# 411618_029_3_5.net
KiCad netlist of a schematic drawn in Altium Designer
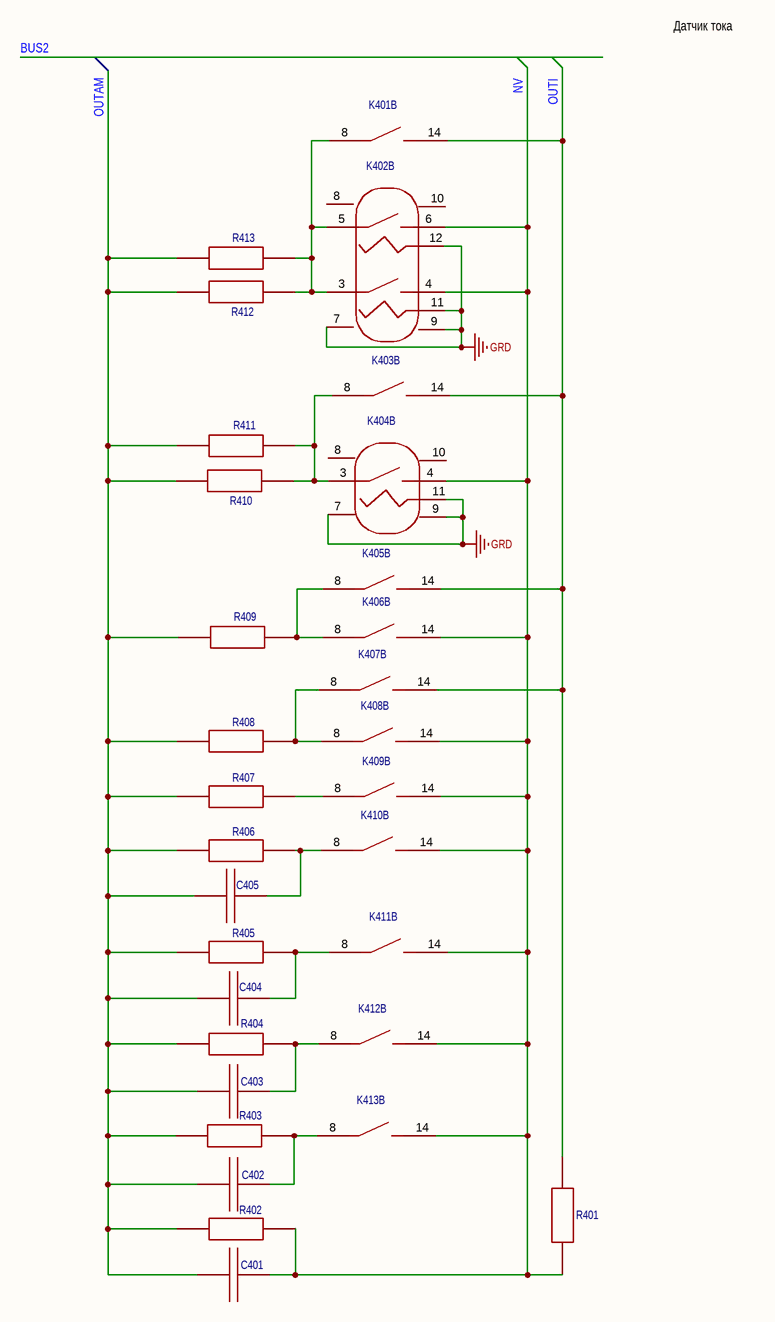
[diagram p0: УШЯИ.411618.029Э Э3 Лист 5.schdoc]

(export (version "E")
  (design (tool "Eeschema 10.0.6"))
  (components
    (comp (ref "C401")
      (value "Конденсатор К10-17Б М47 33пФ NP0 5% [DIP]")
      (footprint "Конденсатор К10-17Б М47 X.X.xФ  NP0 5% [DIP 8мм]")
      (fields (field (name "MANUFACTURER PART") "К10-17Б М47") (field (name "CONTRIBUTOR") "jordanjin"))
      (libsource (lib "altium-import") (part "root_2_Конденсатор К10-17Б М47 33пФ NP0 5% [DIP]_"))
    )
    (comp (ref "C402")
      (value "Конденсатор К10-17Б М47 33пФ NP0 5% [DIP]")
      (footprint "Конденсатор К10-17Б М47 X.X.xФ  NP0 5% [DIP 5мм]")
      (fields (field (name "MANUFACTURER PART") "К10-17Б М47") (field (name "CONTRIBUTOR") "jordanjin"))
      (libsource (lib "altium-import") (part "root_2_Конденсатор К10-17Б М47 33пФ NP0 5% [DIP]_"))
    )
    (comp (ref "C403")
      (value "Конденсатор К10-17Б М47 33пФ NP0 5% [DIP]")
      (footprint "Конденсатор К10-17Б М47 X.X.xФ  NP0 5% [DIP 5мм]")
      (fields (field (name "MANUFACTURER PART") "К10-17Б М47") (field (name "CONTRIBUTOR") "jordanjin"))
      (libsource (lib "altium-import") (part "root_2_Конденсатор К10-17Б М47 33пФ NP0 5% [DIP]_"))
    )
    (comp (ref "C404")
      (value "Конденсатор К10-17Б М47 33пФ NP0 5% [DIP]")
      (footprint "Конденсатор К10-17Б М47 X.X.xФ  NP0 5% [DIP 5мм]")
      (fields (field (name "MANUFACTURER PART") "К10-17Б М47") (field (name "CONTRIBUTOR") "jordanjin"))
      (libsource (lib "altium-import") (part "root_2_Конденсатор К10-17Б М47 33пФ NP0 5% [DIP]_"))
    )
    (comp (ref "C405")
      (value "Конденсатор К10-17Б М47 33пФ NP0 5% [DIP]")
      (footprint "Конденсатор К10-17Б М47 X.X.xФ  NP0 5% [DIP 5мм]")
      (fields (field (name "MANUFACTURER PART") "К10-17Б М47") (field (name "CONTRIBUTOR") "jordanjin"))
      (libsource (lib "altium-import") (part "root_2_Конденсатор К10-17Б М47 33пФ NP0 5% [DIP]_"))
    )
    (comp (ref "K401")
      (value "Реле герконовое DIP05-1A72-13L  [PCB]")
      (footprint "RELAY-TH_STANDEXMEDER_DIP05-1A72-13L")
      (fields
        (field (name "MANUFACTURER") "STANDEXMEDER")
        (field (name "MANUFACTURER PART") "DIP05-1A72-13L")
        (field (name "SUBPART_NO") "1")
        (field (name "CONTRIBUTOR") "jordanjin")
      )
      (libsource (lib "altium-import") (part "root_1_Реле герконовое DIP05-1A72-13L  [PCB]_"))
    )
    (comp (ref "K402")
      (value "Реле герконовое УШЯИ.685442.092 (2 реле)")
      (fields
        (field (name "MANUFACTURER") "ОАО\"МНИПИ\"")
        (field (name "MANUFACTURER PART") "УШЯИ.685442.092")
        (field (name "PART NUMBER") "1")
        (field (name "CONTRIBUTOR") "jordanjin")
      )
      (libsource (lib "altium-import") (part "root_1_Реле герконовое УШЯИ.685442.092 (2 реле)_"))
    )
    (comp (ref "K403")
      (value "Реле герконовое DIP05-1A72-13L  [PCB]")
      (footprint "RELAY-TH_STANDEXMEDER_DIP05-1A72-13L")
      (fields
        (field (name "MANUFACTURER") "STANDEXMEDER")
        (field (name "MANUFACTURER PART") "DIP05-1A72-13L")
        (field (name "SUBPART_NO") "1")
        (field (name "CONTRIBUTOR") "jordanjin")
      )
      (libsource (lib "altium-import") (part "root_1_Реле герконовое DIP05-1A72-13L  [PCB]_"))
    )
    (comp (ref "K404")
      (value "Реле герконовое УШЯИ.685442.092 (1 реле)")
      (fields
        (field (name "MANUFACTURER") "ОАО\"МНИПИ\"")
        (field (name "MANUFACTURER PART") "УШЯИ.685442.092")
        (field (name "SUBPART_NO") "1")
        (field (name "CONTRIBUTOR") "jordanjin")
      )
      (libsource (lib "altium-import") (part "root_1_Реле герконовое УШЯИ.685442.092 (1 реле)_"))
    )
    (comp (ref "K405")
      (value "Реле герконовое DIP05-1A72-13L  [PCB]")
      (footprint "RELAY-TH_STANDEXMEDER_DIP05-1A72-13L")
      (fields
        (field (name "MANUFACTURER") "STANDEXMEDER")
        (field (name "MANUFACTURER PART") "DIP05-1A72-13L")
        (field (name "SUBPART_NO") "1")
        (field (name "CONTRIBUTOR") "jordanjin")
      )
      (libsource (lib "altium-import") (part "root_1_Реле герконовое DIP05-1A72-13L  [PCB]_"))
    )
    (comp (ref "K406")
      (value "Реле герконовое DIP05-1A72-13L  [PCB]")
      (footprint "RELAY-TH_STANDEXMEDER_DIP05-1A72-13L")
      (fields
        (field (name "MANUFACTURER") "STANDEXMEDER")
        (field (name "MANUFACTURER PART") "DIP05-1A72-13L")
        (field (name "SUBPART_NO") "1")
        (field (name "CONTRIBUTOR") "jordanjin")
      )
      (libsource (lib "altium-import") (part "root_1_Реле герконовое DIP05-1A72-13L  [PCB]_"))
    )
    (comp (ref "K407")
      (value "Реле герконовое DIP05-1A72-13L  [PCB]")
      (footprint "RELAY-TH_STANDEXMEDER_DIP05-1A72-13L")
      (fields
        (field (name "MANUFACTURER") "STANDEXMEDER")
        (field (name "MANUFACTURER PART") "DIP05-1A72-13L")
        (field (name "SUBPART_NO") "1")
        (field (name "CONTRIBUTOR") "jordanjin")
      )
      (libsource (lib "altium-import") (part "root_1_Реле герконовое DIP05-1A72-13L  [PCB]_"))
    )
    (comp (ref "K408")
      (value "Реле герконовое DIP05-1A72-13L  [PCB]")
      (footprint "RELAY-TH_STANDEXMEDER_DIP05-1A72-13L")
      (fields
        (field (name "MANUFACTURER") "STANDEXMEDER")
        (field (name "MANUFACTURER PART") "DIP05-1A72-13L")
        (field (name "SUBPART_NO") "1")
        (field (name "CONTRIBUTOR") "jordanjin")
      )
      (libsource (lib "altium-import") (part "root_1_Реле герконовое DIP05-1A72-13L  [PCB]_"))
    )
    (comp (ref "K409")
      (value "Реле герконовое DIP05-1A72-13L  [PCB]")
      (footprint "RELAY-TH_STANDEXMEDER_DIP05-1A72-13L")
      (fields
        (field (name "MANUFACTURER") "STANDEXMEDER")
        (field (name "MANUFACTURER PART") "DIP05-1A72-13L")
        (field (name "SUBPART_NO") "1")
        (field (name "CONTRIBUTOR") "jordanjin")
      )
      (libsource (lib "altium-import") (part "root_1_Реле герконовое DIP05-1A72-13L  [PCB]_"))
    )
    (comp (ref "K410")
      (value "Реле герконовое DIP05-1A72-13L  [PCB]")
      (footprint "RELAY-TH_STANDEXMEDER_DIP05-1A72-13L")
      (fields
        (field (name "MANUFACTURER") "STANDEXMEDER")
        (field (name "MANUFACTURER PART") "DIP05-1A72-13L")
        (field (name "SUBPART_NO") "1")
        (field (name "CONTRIBUTOR") "jordanjin")
      )
      (libsource (lib "altium-import") (part "root_1_Реле герконовое DIP05-1A72-13L  [PCB]_"))
    )
    (comp (ref "K411")
      (value "Реле герконовое DIP05-1A72-13L  [PCB]")
      (footprint "RELAY-TH_STANDEXMEDER_DIP05-1A72-13L")
      (fields
        (field (name "MANUFACTURER") "STANDEXMEDER")
        (field (name "MANUFACTURER PART") "DIP05-1A72-13L")
        (field (name "SUBPART_NO") "1")
        (field (name "CONTRIBUTOR") "jordanjin")
      )
      (libsource (lib "altium-import") (part "root_1_Реле герконовое DIP05-1A72-13L  [PCB]_"))
    )
    (comp (ref "K412")
      (value "Реле герконовое DIP05-1A72-13L  [PCB]")
      (footprint "RELAY-TH_STANDEXMEDER_DIP05-1A72-13L")
      (fields
        (field (name "MANUFACTURER") "STANDEXMEDER")
        (field (name "MANUFACTURER PART") "DIP05-1A72-13L")
        (field (name "SUBPART_NO") "1")
        (field (name "CONTRIBUTOR") "jordanjin")
      )
      (libsource (lib "altium-import") (part "root_1_Реле герконовое DIP05-1A72-13L  [PCB]_"))
    )
    (comp (ref "K413")
      (value "Реле герконовое DIP05-1A72-13L  [PCB]")
      (footprint "RELAY-TH_STANDEXMEDER_DIP05-1A72-13L")
      (fields
        (field (name "MANUFACTURER") "STANDEXMEDER")
        (field (name "MANUFACTURER PART") "DIP05-1A72-13L")
        (field (name "SUBPART_NO") "1")
        (field (name "CONTRIBUTOR") "jordanjin")
      )
      (libsource (lib "altium-import") (part "root_1_Реле герконовое DIP05-1A72-13L  [PCB]_"))
    )
    (comp (ref "R401")
      (value "Резистор C2-29В-0,25  24кОм ±0,5% [DIP]")
      (fields (field (name "MANUFACTURER PART") "C2-29В-0,25") (field (name "CONTRIBUTOR") "jordanjin"))
      (libsource (lib "altium-import") (part "root_1_Резистор C2-29В-0,25  24кОм ±0,5% [DIP]_"))
    )
    (comp (ref "R402")
      (value "Резистор SM204031006FE 100МОм ±1%[DIP]")
      (footprint "RES-TH_L27.4-W2.5-P22.86-D0.8")
      (fields
        (field (name "MANUFACTURER") "Ohmite")
        (field (name "MANUFACTURER PART") "SM204031006FE")
        (field (name "CONTRIBUTOR") "jordanjin")
      )
      (libsource (lib "altium-import") (part "root_2_Резистор SM204031006FE 100МОм ±1%[DIP]_"))
    )
    (comp (ref "R403")
      (value "Резистор RK1/4DCT52R1105F 11 МОм ±1% [DIP]")
      (fields
        (field (name "MANUFACTURER") "KOA Speer Electronics")
        (field (name "MANUFACTURER PART") "RK1/4DCT52R1105F")
        (field (name "CONTRIBUTOR") "jordanjin")
      )
      (libsource (lib "altium-import") (part "root_2_Резистор RK1/4DCT52R1105F 11 МОм ±1% [DIP]_"))
    )
    (comp (ref "R404")
      (value "Резистор C2-29В-0,25 1 МОм ±0,5% [DIP]")
      (fields (field (name "MANUFACTURER PART") "C2-29В-0,25") (field (name "CONTRIBUTOR") "jordanjin"))
      (libsource (lib "altium-import") (part "root_2_Резистор C2-29В-0,25 1 МОм ±0,5% [DIP]_"))
    )
    (comp (ref "R405")
      (value "Резистор C2-29В-0,25 100 кОм ±0,5% [DIP]")
      (fields (field (name "MANUFACTURER PART") "C2-29В-0,25") (field (name "CONTRIBUTOR") "jordanjin"))
      (libsource (lib "altium-import") (part "root_2_Резистор C2-29В-0,25 100 кОм ±0,5% [DIP]_"))
    )
    (comp (ref "R406")
      (value "Резистор C2-29B-1 10 кОм ±0,5% [DIP]")
      (fields (field (name "MANUFACTURER PART") "C2-29В-1") (field (name "CONTRIBUTOR") "jordanjin"))
      (libsource (lib "altium-import") (part "root_2_Резистор C2-29B-1 10 кОм ±0,5% [DIP]_"))
    )
    (comp (ref "R407")
      (value "Резистор C2-29B-1 1 кОм ±0,5% [DIP]")
      (fields (field (name "MANUFACTURER PART") "C2-29В-1") (field (name "CONTRIBUTOR") "jordanjin"))
      (libsource (lib "altium-import") (part "root_2_Резистор C2-29B-1 1 кОм ±0,5% [DIP]_"))
    )
    (comp (ref "R408")
      (value "Резистор C2-29B-1 100 Ом ±0,5% [DIP]")
      (fields (field (name "MANUFACTURER PART") "C2-29В-1") (field (name "CONTRIBUTOR") "jordanjin"))
      (libsource (lib "altium-import") (part "root_2_Резистор C2-29B-1 100 Ом ±0,5% [DIP]_"))
    )
    (comp (ref "R409")
      (value "Резистор C2-29B-2 10 Ом ±0,5% [DIP]")
      (fields (field (name "MANUFACTURER PART") "C2-29В-2") (field (name "CONTRIBUTOR") "jordanjin"))
      (libsource (lib "altium-import") (part "root_2_Резистор C2-29B-2 10 Ом ±0,5% [DIP]_"))
    )
    (comp (ref "R410")
      (value "Резистор MP930-2.00-1% [TO-220-2]")
      (footprint "TO-220-2_L10.4-W3.2-P5.08-L")
      (fields
        (field (name "MANUFACTURER") "Caddock")
        (field (name "MANUFACTURER PART") "MP930-2.00-1%")
        (field (name "CONTRIBUTOR") "jordanjin")
      )
      (libsource (lib "altium-import") (part "root_2_Резистор MP930-2.00-1% [TO-220-2]_"))
    )
    (comp (ref "R411")
      (value "Резистор MP930-2.00-1% [TO-220-2]")
      (footprint "TO-220-2_L10.4-W3.2-P5.08-L")
      (fields
        (field (name "MANUFACTURER") "Caddock")
        (field (name "MANUFACTURER PART") "MP930-2.00-1%")
        (field (name "CONTRIBUTOR") "jordanjin")
      )
      (libsource (lib "altium-import") (part "root_2_Резистор MP930-2.00-1% [TO-220-2]_"))
    )
    (comp (ref "R412")
      (value "Резистор MP930-0.20-1% [TO-220-2]")
      (footprint "TO-220-2_L10.4-W3.2-P5.08-L")
      (fields
        (field (name "MANUFACTURER") "Caddock")
        (field (name "MANUFACTURER PART") "MP930-2.00-1%")
        (field (name "CONTRIBUTOR") "jordanjin")
      )
      (libsource (lib "altium-import") (part "root_2_Резистор MP930-0.20-1% [TO-220-2]_"))
    )
    (comp (ref "R413")
      (value "Резистор MP930-0.20-1% [TO-220-2]")
      (footprint "TO-220-2_L10.4-W3.2-P5.08-L")
      (fields
        (field (name "MANUFACTURER") "Caddock")
        (field (name "MANUFACTURER PART") "MP930-2.00-1%")
        (field (name "CONTRIBUTOR") "jordanjin")
      )
      (libsource (lib "altium-import") (part "root_2_Резистор MP930-0.20-1% [TO-220-2]_"))
    )
  )
  (nets
    (net (code "2") (name "/NV") (class "Default")
      (node (ref "C401") (pin "1") (pinfunction "1_1") (pintype "passive"))
      (node (ref "K402") (pin "4") (pinfunction "4_4") (pintype "passive"))
      (node (ref "K402") (pin "6") (pinfunction "6_6") (pintype "passive"))
      (node (ref "K404") (pin "4") (pinfunction "4_4") (pintype "passive"))
      (node (ref "K406") (pin "14") (pinfunction "14_14") (pintype "passive"))
      (node (ref "K408") (pin "14") (pinfunction "14_14") (pintype "passive"))
      (node (ref "K409") (pin "14") (pinfunction "14_14") (pintype "passive"))
      (node (ref "K410") (pin "14") (pinfunction "14_14") (pintype "passive"))
      (node (ref "K411") (pin "14") (pinfunction "14_14") (pintype "passive"))
      (node (ref "K412") (pin "14") (pinfunction "14_14") (pintype "passive"))
      (node (ref "K413") (pin "14") (pinfunction "14_14") (pintype "passive"))
      (node (ref "R401") (pin "1") (pinfunction "1_1") (pintype "passive"))
      (node (ref "R402") (pin "1") (pinfunction "1_1") (pintype "passive"))
    )
    (net (code "3") (name "/OUTAM") (class "Default")
      (node (ref "C401") (pin "2") (pinfunction "2_2") (pintype "passive"))
      (node (ref "C402") (pin "2") (pinfunction "2_2") (pintype "passive"))
      (node (ref "C403") (pin "2") (pinfunction "2_2") (pintype "passive"))
      (node (ref "C404") (pin "2") (pinfunction "2_2") (pintype "passive"))
      (node (ref "C405") (pin "2") (pinfunction "2_2") (pintype "passive"))
      (node (ref "R402") (pin "2") (pinfunction "2_2") (pintype "passive"))
      (node (ref "R403") (pin "2") (pinfunction "2_2") (pintype "passive"))
      (node (ref "R404") (pin "2") (pinfunction "2_2") (pintype "passive"))
      (node (ref "R405") (pin "2") (pinfunction "2_2") (pintype "passive"))
      (node (ref "R406") (pin "2") (pinfunction "2_2") (pintype "passive"))
      (node (ref "R407") (pin "2") (pinfunction "2_2") (pintype "passive"))
      (node (ref "R408") (pin "2") (pinfunction "2_2") (pintype "passive"))
      (node (ref "R409") (pin "2") (pinfunction "2_2") (pintype "passive"))
      (node (ref "R410") (pin "2") (pinfunction "2_2") (pintype "passive"))
      (node (ref "R411") (pin "2") (pinfunction "2_2") (pintype "passive"))
      (node (ref "R412") (pin "2") (pinfunction "2_2") (pintype "passive"))
      (node (ref "R413") (pin "2") (pinfunction "2_2") (pintype "passive"))
    )
    (net (code "4") (name "/OUTI") (class "Default")
      (node (ref "K401") (pin "14") (pinfunction "14_14") (pintype "passive"))
      (node (ref "K403") (pin "14") (pinfunction "14_14") (pintype "passive"))
      (node (ref "K405") (pin "14") (pinfunction "14_14") (pintype "passive"))
      (node (ref "K407") (pin "14") (pinfunction "14_14") (pintype "passive"))
      (node (ref "R401") (pin "2") (pinfunction "2_2") (pintype "passive"))
    )
    (net (code "6") (name "GRD") (class "Default")
      (node (ref "K402") (pin "11") (pinfunction "11_11") (pintype "passive"))
      (node (ref "K402") (pin "12") (pinfunction "12_12") (pintype "passive"))
      (node (ref "K402") (pin "7") (pinfunction "7_7") (pintype "passive"))
      (node (ref "K402") (pin "9") (pinfunction "9_9") (pintype "passive"))
      (node (ref "K404") (pin "11") (pinfunction "11_11") (pintype "passive"))
      (node (ref "K404") (pin "7") (pinfunction "7_7") (pintype "passive"))
      (node (ref "K404") (pin "9") (pinfunction "9_9") (pintype "passive"))
    )
    (net (code "7") (name "Net-(C402-Pad1)") (class "Default")
      (node (ref "C402") (pin "1") (pinfunction "1_1") (pintype "passive"))
      (node (ref "K413") (pin "8") (pinfunction "8_8") (pintype "passive"))
      (node (ref "R403") (pin "1") (pinfunction "1_1") (pintype "passive"))
    )
    (net (code "8") (name "Net-(C403-Pad1)") (class "Default")
      (node (ref "C403") (pin "1") (pinfunction "1_1") (pintype "passive"))
      (node (ref "K412") (pin "8") (pinfunction "8_8") (pintype "passive"))
      (node (ref "R404") (pin "1") (pinfunction "1_1") (pintype "passive"))
    )
    (net (code "9") (name "Net-(C404-Pad1)") (class "Default")
      (node (ref "C404") (pin "1") (pinfunction "1_1") (pintype "passive"))
      (node (ref "K411") (pin "8") (pinfunction "8_8") (pintype "passive"))
      (node (ref "R405") (pin "1") (pinfunction "1_1") (pintype "passive"))
    )
    (net (code "10") (name "Net-(C405-Pad1)") (class "Default")
      (node (ref "C405") (pin "1") (pinfunction "1_1") (pintype "passive"))
      (node (ref "K410") (pin "8") (pinfunction "8_8") (pintype "passive"))
      (node (ref "R406") (pin "1") (pinfunction "1_1") (pintype "passive"))
    )
    (net (code "11") (name "Net-(K401-Pad8)") (class "Default")
      (node (ref "K401") (pin "8") (pinfunction "8_8") (pintype "passive"))
      (node (ref "K402") (pin "3") (pinfunction "3_3") (pintype "passive"))
      (node (ref "K402") (pin "5") (pinfunction "5_5") (pintype "passive"))
      (node (ref "R412") (pin "1") (pinfunction "1_1") (pintype "passive"))
      (node (ref "R413") (pin "1") (pinfunction "1_1") (pintype "passive"))
    )
    (net (code "12") (name "Net-(K403-Pad8)") (class "Default")
      (node (ref "K403") (pin "8") (pinfunction "8_8") (pintype "passive"))
      (node (ref "K404") (pin "3") (pinfunction "3_3") (pintype "passive"))
      (node (ref "R410") (pin "1") (pinfunction "1_1") (pintype "passive"))
      (node (ref "R411") (pin "1") (pinfunction "1_1") (pintype "passive"))
    )
    (net (code "13") (name "Net-(K405-Pad8)") (class "Default")
      (node (ref "K405") (pin "8") (pinfunction "8_8") (pintype "passive"))
      (node (ref "K406") (pin "8") (pinfunction "8_8") (pintype "passive"))
      (node (ref "R409") (pin "1") (pinfunction "1_1") (pintype "passive"))
    )
    (net (code "14") (name "Net-(K407-Pad8)") (class "Default")
      (node (ref "K407") (pin "8") (pinfunction "8_8") (pintype "passive"))
      (node (ref "K408") (pin "8") (pinfunction "8_8") (pintype "passive"))
      (node (ref "R408") (pin "1") (pinfunction "1_1") (pintype "passive"))
    )
    (net (code "15") (name "Net-(K409-Pad8)") (class "Default")
      (node (ref "K409") (pin "8") (pinfunction "8_8") (pintype "passive"))
      (node (ref "R407") (pin "1") (pinfunction "1_1") (pintype "passive"))
    )
    (net (code "16") (name "unconnected-(K402-Pad8)") (class "Default")
      (node (ref "K402") (pin "8") (pinfunction "8_8") (pintype "passive"))
    )
    (net (code "17") (name "unconnected-(K402-Pad10)") (class "Default")
      (node (ref "K402") (pin "10") (pinfunction "10_10") (pintype "passive"))
    )
    (net (code "18") (name "unconnected-(K404-Pad8)") (class "Default")
      (node (ref "K404") (pin "8") (pinfunction "8_8") (pintype "passive"))
    )
    (net (code "19") (name "unconnected-(K404-Pad10)") (class "Default")
      (node (ref "K404") (pin "10") (pinfunction "10_10") (pintype "passive"))
    )
  )
)
